# MAX17502.net
KiCad netlist of a schematic drawn in Altium Designer
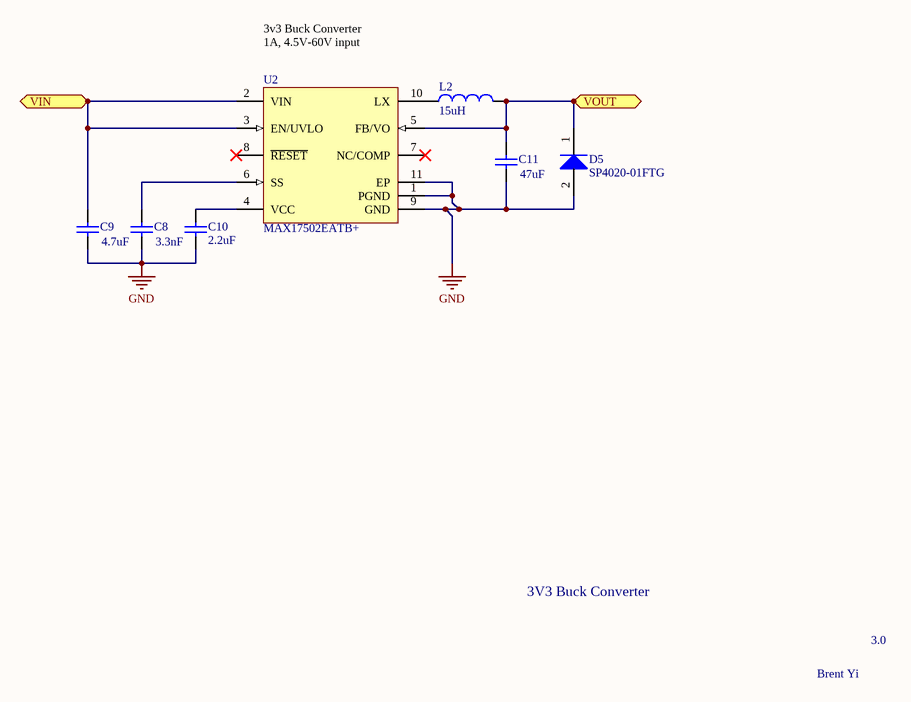
[diagram p0: MAX17502.SchDoc]

(export (version "E")
  (design (tool "Eeschema 10.0.6"))
  (components
    (comp (ref "C8")
      (value "3.3nF")
      (footprint "CAPC0603(1608)55_N")
      (description "CAP 2.2uF 16V Â±10% 0603 (1608 Metric) Thickness 0.55mm SMD")
      (fields (field (name "TOLERANCE") "Â±10%"))
      (libsource (lib "Altium Content Vault") (part "CMP-1035-02762-1"))
    )
    (comp (ref "C9")
      (value "4.7uF")
      (footprint "CAPC1210(3225)280_N")
      (description "CAP 100uF 10V Â±10% 1210 (3225 Metric) Thickness 2.8mm SMD")
      (fields (field (name "TOLERANCE") "Â±10%"))
      (libsource (lib "Altium Content Vault") (part "CMP-1038-02301-1"))
    )
    (comp (ref "C10")
      (value "2.2uF")
      (footprint "CAPC0603(1608)100_N")
      (description "CAP 1uF 6.3V Â±10% 0603 (1608 Metric) Thickness 1mm SMD")
      (fields (field (name "TOLERANCE") "Â±10%"))
      (libsource (lib "Altium Content Vault") (part "CMP-1035-02730-1"))
    )
    (comp (ref "C11")
      (value "47uF")
      (footprint "CAPC1210(3225)280_N")
      (description "CAP 100uF 10V Â±10% 1210 (3225 Metric) Thickness 2.8mm SMD")
      (fields (field (name "TOLERANCE") "Â±10%"))
      (libsource (lib "Altium Content Vault") (part "CMP-1038-02301-1"))
    )
    (comp (ref "D5")
      (value "SP4020-01FTG")
      (footprint "SOD323")
      (fields (field (name "PARTNUMBER") "MMSZ5262BT1G") (field (name "MANUFACTURER") "On Semiconductor"))
      (libsource (lib "Components") (part "SP4020-01FTG"))
    )
    (comp (ref "L2")
      (value "15uH")
      (footprint "SDR0604")
      (description "Inductor")
      (fields (field (name "Comment") "SDR0805-180ML") (field (name "PUBLISHER") "Altium Limited"))
      (libsource (lib "Components") (part "SDR0805-180ML"))
    )
    (comp (ref "U2")
      (value "MAX17502EATB+")
      (footprint "MAXM-T1032N+1_V")
      (fields (field (name "MANUFACTURER") "Maxim"))
      (libsource (lib "Altium Content Vault") (part "MAXM-MAX17502-10"))
    )
  )
  (nets
    (net (code "1") (name "/VIN") (class "Default")
      (node (ref "C9") (pin "2") (pinfunction "2_2") (pintype "passive"))
      (node (ref "U2") (pin "2") (pinfunction "VIN_2") (pintype "power_in"))
      (node (ref "U2") (pin "3") (pinfunction "EN/UVLO_3") (pintype "input"))
    )
    (net (code "2") (name "/VOUT") (class "Default")
      (node (ref "C11") (pin "2") (pinfunction "2_2") (pintype "passive"))
      (node (ref "D5") (pin "1") (pinfunction "K_1") (pintype "passive"))
      (node (ref "L2") (pin "2") (pinfunction "2_2") (pintype "passive"))
      (node (ref "U2") (pin "5") (pinfunction "FB/VO_5") (pintype "input"))
    )
    (net (code "3") (name "GND") (class "Default")
      (node (ref "C10") (pin "2") (pinfunction "2_2") (pintype "passive"))
      (node (ref "C11") (pin "1") (pinfunction "1_1") (pintype "passive"))
      (node (ref "C8") (pin "2") (pinfunction "2_2") (pintype "passive"))
      (node (ref "C9") (pin "1") (pinfunction "1_1") (pintype "passive"))
      (node (ref "D5") (pin "2") (pinfunction "A_2") (pintype "passive"))
      (node (ref "U2") (pin "1") (pinfunction "PGND_1") (pintype "power_in"))
      (node (ref "U2") (pin "11") (pinfunction "EP_11") (pintype "power_in"))
      (node (ref "U2") (pin "9") (pinfunction "GND_9") (pintype "power_in"))
    )
    (net (code "4") (name "Net-(U2-LX)") (class "Default")
      (node (ref "L2") (pin "1") (pinfunction "1_1") (pintype "passive"))
      (node (ref "U2") (pin "10") (pinfunction "LX_10") (pintype "passive"))
    )
    (net (code "5") (name "Net-(U2-SS)") (class "Default")
      (node (ref "C8") (pin "1") (pinfunction "1_1") (pintype "passive"))
      (node (ref "U2") (pin "6") (pinfunction "SS_6") (pintype "input"))
    )
    (net (code "6") (name "Net-(U2-VCC)") (class "Default")
      (node (ref "C10") (pin "1") (pinfunction "1_1") (pintype "passive"))
      (node (ref "U2") (pin "4") (pinfunction "VCC_4") (pintype "power_in"))
    )
    (net (code "7") (name "unconnected-(U2-NC{slash}COMP-Pad7)") (class "Default")
      (node (ref "U2") (pin "7") (pinfunction "NC/COMP_7") (pintype "passive+no_connect"))
    )
    (net (code "8") (name "unconnected-(U2-~{RESET}-Pad8)") (class "Default")
      (node (ref "U2") (pin "8") (pinfunction "~{RESET}_8") (pintype "open_collector+no_connect"))
    )
  )
)
